# PBASE420.net
KiCad netlist of a schematic drawn in EAGLE
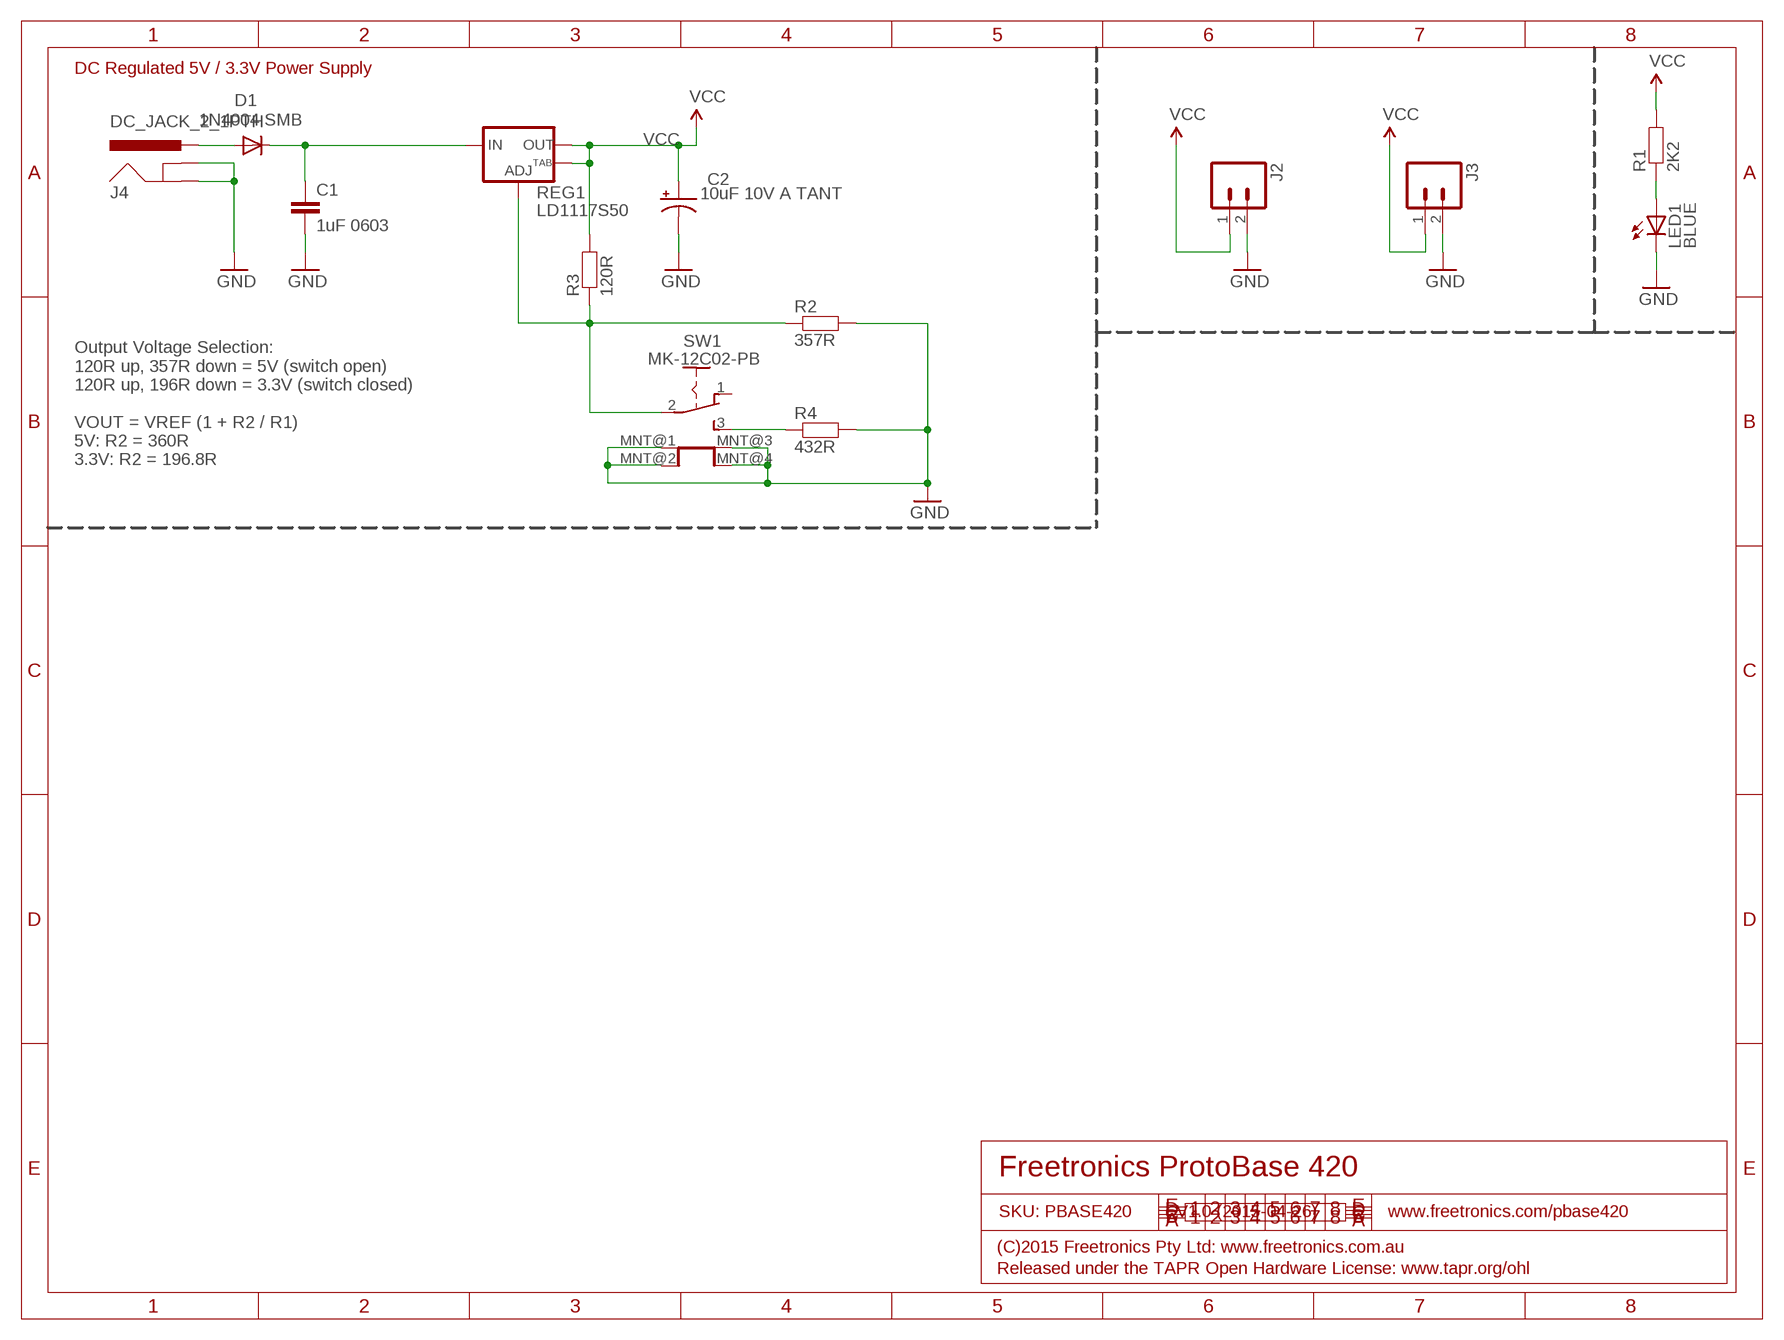
[diagram p0: schematic, sheet 1]

(export (version "E")
  (design (tool "Eeschema 10.0.6"))
  (components
    (comp (ref "C1")
      (value "1uF 0603")
      (footprint "eagle-import:0603")
      (libsource (lib "eagle-import") (part "CAP0603"))
    )
    (comp (ref "C2")
      (value "10uF 10V A TANT")
      (footprint "eagle-import:EIA3216")
      (libsource (lib "eagle-import") (part "CAP_POL1206"))
    )
    (comp (ref "D1")
      (value "1N4004 SMB")
      (footprint "eagle-import:SMB-DIODE")
      (libsource (lib "eagle-import") (part "DIODESMB"))
    )
    (comp (ref "J2")
      (value "M02PTH")
      (footprint "eagle-import:1X02")
      (libsource (lib "eagle-import") (part "M02PTH"))
    )
    (comp (ref "J3")
      (value "M02PTH")
      (footprint "eagle-import:1X02")
      (libsource (lib "eagle-import") (part "M02PTH"))
    )
    (comp (ref "J4")
      (value "DC_JACK_2_1PTH")
      (footprint "eagle-import:FREETRONICS_POWER_JACK_PTH")
      (libsource (lib "eagle-import") (part "DC_JACK_2_1PTH"))
    )
    (comp (ref "LED1")
      (value "BLUE")
      (footprint "eagle-import:LED-0603")
      (libsource (lib "eagle-import") (part "LED0603"))
    )
    (comp (ref "R1")
      (value "2K2")
      (footprint "eagle-import:0603")
      (libsource (lib "eagle-import") (part "RESISTOR0603"))
    )
    (comp (ref "R2")
      (value "357R")
      (footprint "eagle-import:0603")
      (libsource (lib "eagle-import") (part "RESISTOR0603"))
    )
    (comp (ref "R3")
      (value "120R")
      (footprint "eagle-import:0603")
      (libsource (lib "eagle-import") (part "RESISTOR0603"))
    )
    (comp (ref "R4")
      (value "432R")
      (footprint "eagle-import:0603")
      (libsource (lib "eagle-import") (part "RESISTOR0603"))
    )
    (comp (ref "REG1")
      (value "LD1117S50")
      (footprint "eagle-import:SOT223")
      (libsource (lib "eagle-import") (part "V_REG_LM1117SOT223"))
    )
    (comp (ref "SW1")
      (value "MK-12C02-PB")
      (footprint "eagle-import:MK-12C02")
      (libsource (lib "eagle-import") (part "SWITCH-SPDT-4TABSSMT"))
    )
  )
  (nets
    (net (code "1") (name "GND") (class "Default")
      (node (ref "C1") (pin "2") (pinfunction "2_2") (pintype "passive"))
      (node (ref "C2") (pin "C") (pinfunction "-_C") (pintype "passive"))
      (node (ref "J2") (pin "2") (pinfunction "2_2") (pintype "passive"))
      (node (ref "J3") (pin "2") (pinfunction "2_2") (pintype "passive"))
      (node (ref "J4") (pin "GND@1") (pinfunction "GND_GND@1") (pintype "bidirectional"))
      (node (ref "J4") (pin "GND@2") (pinfunction "GND_GND@2") (pintype "bidirectional"))
      (node (ref "J4") (pin "GNDBREAK@1") (pinfunction "GNDBREAK_GNDBREAK@1") (pintype "bidirectional"))
      (node (ref "J4") (pin "GNDBREAK@2") (pinfunction "GNDBREAK_GNDBREAK@2") (pintype "bidirectional"))
      (node (ref "LED1") (pin "C") (pinfunction "C_C") (pintype "passive"))
      (node (ref "R2") (pin "2") (pinfunction "2_2") (pintype "passive"))
      (node (ref "R4") (pin "2") (pinfunction "2_2") (pintype "passive"))
      (node (ref "SW1") (pin "MNT@1") (pinfunction "MNT_MNT@1") (pintype "bidirectional"))
      (node (ref "SW1") (pin "MNT@2") (pinfunction "MNT_MNT@2") (pintype "bidirectional"))
      (node (ref "SW1") (pin "MNT@3") (pinfunction "MNT_MNT@3") (pintype "bidirectional"))
      (node (ref "SW1") (pin "MNT@4") (pinfunction "MNT_MNT@4") (pintype "bidirectional"))
    )
    (net (code "2") (name "Net-(D1-PadA)") (class "Default")
      (node (ref "D1") (pin "A") (pinfunction "A_A") (pintype "passive"))
      (node (ref "J4") (pin "PWR@1") (pinfunction "PWR_PWR@1") (pintype "bidirectional"))
      (node (ref "J4") (pin "PWR@2") (pinfunction "PWR_PWR@2") (pintype "bidirectional"))
    )
    (net (code "3") (name "Net-(LED1-PadA)") (class "Default")
      (node (ref "LED1") (pin "A") (pinfunction "A_A") (pintype "passive"))
      (node (ref "R1") (pin "1") (pinfunction "1_1") (pintype "passive"))
    )
    (net (code "4") (name "Net-(REG1-ADJ)") (class "Default")
      (node (ref "R2") (pin "1") (pinfunction "1_1") (pintype "passive"))
      (node (ref "R3") (pin "1") (pinfunction "1_1") (pintype "passive"))
      (node (ref "REG1") (pin "1") (pinfunction "ADJ_1") (pintype "input"))
      (node (ref "SW1") (pin "2") (pinfunction "COM_2") (pintype "passive"))
    )
    (net (code "5") (name "Net-(REG1-IN)") (class "Default")
      (node (ref "C1") (pin "1") (pinfunction "1_1") (pintype "passive"))
      (node (ref "D1") (pin "C") (pinfunction "C_C") (pintype "passive"))
      (node (ref "REG1") (pin "3") (pinfunction "IN_3") (pintype "input"))
    )
    (net (code "6") (name "Net-(SW1-B)") (class "Default")
      (node (ref "R4") (pin "1") (pinfunction "1_1") (pintype "passive"))
      (node (ref "SW1") (pin "3") (pinfunction "B_3") (pintype "passive"))
    )
    (net (code "7") (name "VCC") (class "Default")
      (node (ref "C2") (pin "A") (pinfunction "+_A") (pintype "passive"))
      (node (ref "J2") (pin "1") (pinfunction "1_1") (pintype "passive"))
      (node (ref "J3") (pin "1") (pinfunction "1_1") (pintype "passive"))
      (node (ref "R1") (pin "2") (pinfunction "2_2") (pintype "passive"))
      (node (ref "R3") (pin "2") (pinfunction "2_2") (pintype "passive"))
      (node (ref "REG1") (pin "2") (pinfunction "OUT_2") (pintype "output"))
      (node (ref "REG1") (pin "4") (pinfunction "OUT_4") (pintype "output"))
    )
    (net (code "8") (name "unconnected-(SW1-A-Pad1)") (class "Default")
      (node (ref "SW1") (pin "1") (pinfunction "A_1") (pintype "passive"))
    )
  )
)
